# Tomo.net
KiCad netlist of a schematic drawn in EAGLE
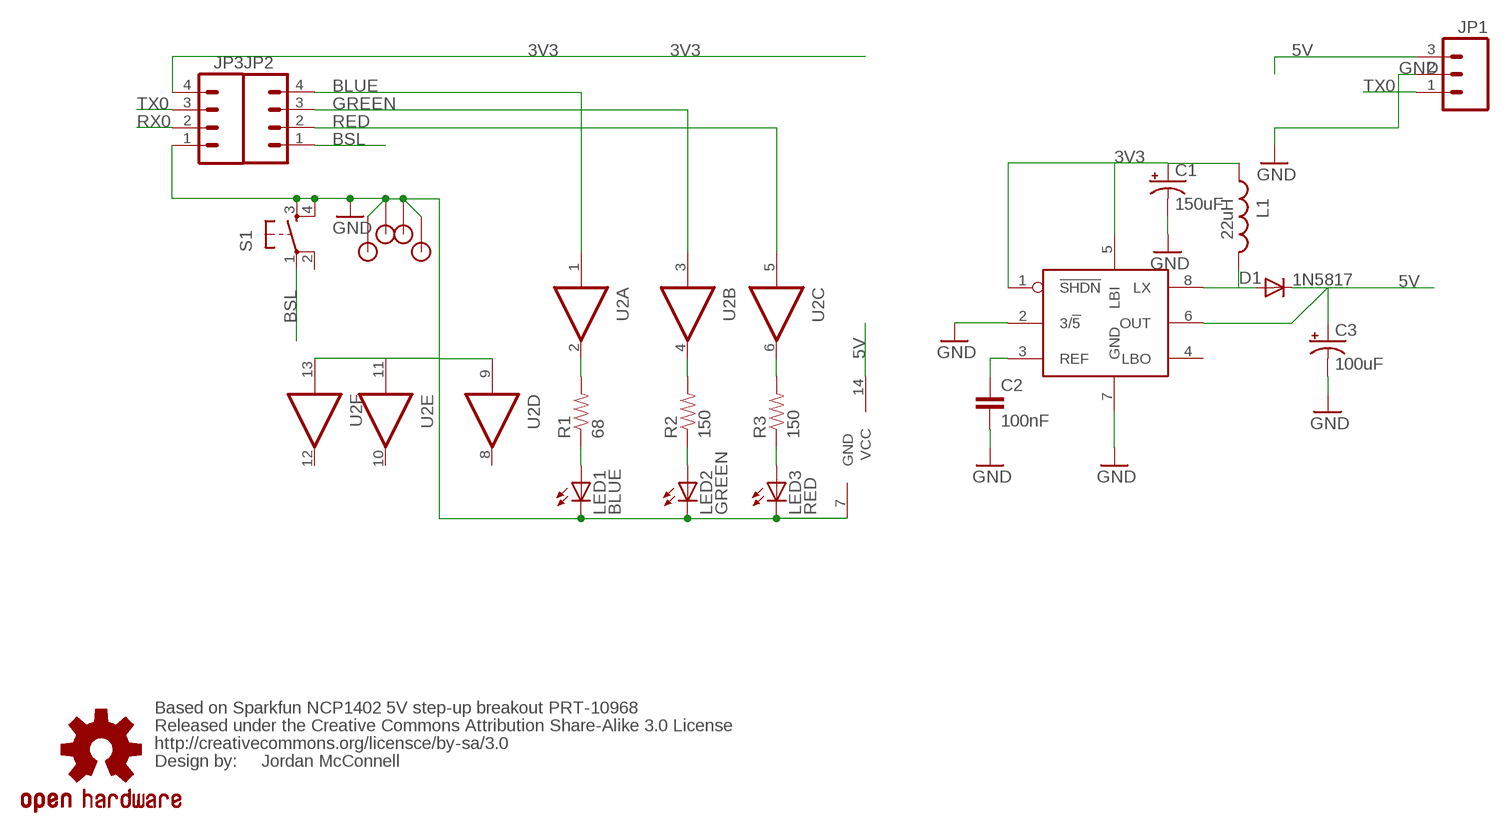
[diagram p0: schematic, sheet 1]

(export (version "E")
  (design (tool "Eeschema 10.0.6"))
  (components
    (comp (ref "C1")
      (value "150uF")
      (footprint "eagle-import:CPOL-RADIAL-100UF-25V")
      (libsource (lib "eagle-import") (part "CAP_POLPTH1"))
    )
    (comp (ref "C2")
      (value "100nF")
      (footprint "eagle-import:CAP-PTH-SMALL")
      (libsource (lib "eagle-import") (part "CAPPTH"))
    )
    (comp (ref "C3")
      (value "100uF")
      (footprint "eagle-import:CPOL-RADIAL-100UF-25V")
      (libsource (lib "eagle-import") (part "CAP_POLPTH1"))
    )
    (comp (ref "D1")
      (value "1N5817")
      (footprint "eagle-import:DIODE-1N4148")
      (libsource (lib "eagle-import") (part "DIODE1N4148"))
    )
    (comp (ref "JP1")
      (value "M03PTH")
      (footprint "eagle-import:1X03")
      (libsource (lib "eagle-import") (part "M03PTH"))
    )
    (comp (ref "JP2")
      (value "M04PTH")
      (footprint "eagle-import:1X04")
      (libsource (lib "eagle-import") (part "M04PTH"))
    )
    (comp (ref "JP3")
      (value "M04PTH")
      (footprint "eagle-import:1X04")
      (libsource (lib "eagle-import") (part "M04PTH"))
    )
    (comp (ref "L1")
      (value "22uH")
      (footprint "eagle-import:RADIAL_5MM")
      (libsource (lib "eagle-import") (part "INDUCTORRCH-895"))
    )
    (comp (ref "LED1")
      (value "BLUE")
      (footprint "eagle-import:LED5MM")
      (libsource (lib "eagle-import") (part "LED5MM"))
    )
    (comp (ref "LED2")
      (value "GREEN")
      (footprint "eagle-import:LED5MM")
      (libsource (lib "eagle-import") (part "LED5MM"))
    )
    (comp (ref "LED3")
      (value "RED")
      (footprint "eagle-import:LED5MM")
      (libsource (lib "eagle-import") (part "LED5MM"))
    )
    (comp (ref "R1")
      (value "68")
      (footprint "eagle-import:AXIAL-0.3")
      (libsource (lib "eagle-import") (part "RESISTORAXIAL-0.3"))
    )
    (comp (ref "R2")
      (value "150")
      (footprint "eagle-import:AXIAL-0.3")
      (libsource (lib "eagle-import") (part "RESISTORAXIAL-0.3"))
    )
    (comp (ref "R3")
      (value "150")
      (footprint "eagle-import:AXIAL-0.3")
      (libsource (lib "eagle-import") (part "RESISTORAXIAL-0.3"))
    )
    (comp (ref "S1")
      (value "TAC_SWITCHPTH")
      (footprint "eagle-import:TACTILE-PTH")
      (libsource (lib "eagle-import") (part "TAC_SWITCHPTH"))
    )
    (comp (ref "U$1")
      (value "OSHW-LOGOL")
      (footprint "eagle-import:OSHW-LOGO-L")
      (libsource (lib "eagle-import") (part "OSHW-LOGOL"))
    )
    (comp (ref "U$2")
      (value "MAX756")
      (footprint "eagle-import:DIL-8")
      (libsource (lib "eagle-import") (part "MAX756"))
    )
    (comp (ref "U$3")
      (value "STANDOFF")
      (footprint "eagle-import:STANDOFF")
      (libsource (lib "eagle-import") (part "STANDOFF"))
    )
    (comp (ref "U$4")
      (value "STANDOFF")
      (footprint "eagle-import:STANDOFF")
      (libsource (lib "eagle-import") (part "STANDOFF"))
    )
    (comp (ref "U$5")
      (value "STANDOFF")
      (footprint "eagle-import:STANDOFF")
      (libsource (lib "eagle-import") (part "STANDOFF"))
    )
    (comp (ref "U$6")
      (value "STANDOFF")
      (footprint "eagle-import:STANDOFF")
      (libsource (lib "eagle-import") (part "STANDOFF"))
    )
    (comp (ref "U2")
      (value "741034")
      (footprint "eagle-import:DIL-14")
      (fields (field (name "DIGIKEY") "296-33703-5-ND"))
      (libsource (lib "eagle-import") (part "741034"))
    )
  )
  (nets
    (net (code "1") (name "/3V3") (class "Default")
      (node (ref "C1") (pin "1") (pinfunction "+_1") (pintype "passive"))
      (node (ref "JP3") (pin "4") (pinfunction "4_4") (pintype "passive"))
      (node (ref "L1") (pin "1") (pinfunction "1_1") (pintype "passive"))
      (node (ref "U$2") (pin "1") (pinfunction "~{SHDN}_1") (pintype "bidirectional"))
      (node (ref "U$2") (pin "5") (pinfunction "LBI_5") (pintype "bidirectional"))
    )
    (net (code "2") (name "/5V") (class "Default")
      (node (ref "C3") (pin "1") (pinfunction "+_1") (pintype "passive"))
      (node (ref "D1") (pin "C") (pinfunction "C_C") (pintype "passive"))
      (node (ref "JP1") (pin "3") (pinfunction "3_3") (pintype "passive"))
      (node (ref "U$2") (pin "6") (pinfunction "OUT_6") (pintype "bidirectional"))
      (node (ref "U2") (pin "14") (pinfunction "VCC_14") (pintype "bidirectional"))
    )
    (net (code "3") (name "/BLUE") (class "Default")
      (node (ref "JP2") (pin "4") (pinfunction "4_4") (pintype "passive"))
      (node (ref "U2") (pin "1") (pinfunction "IN_1") (pintype "input"))
    )
    (net (code "4") (name "/BSL") (class "Default")
      (node (ref "JP2") (pin "1") (pinfunction "1_1") (pintype "passive"))
      (node (ref "S1") (pin "1") (pinfunction "1_1") (pintype "passive"))
    )
    (net (code "5") (name "/GREEN") (class "Default")
      (node (ref "JP2") (pin "3") (pinfunction "3_3") (pintype "passive"))
      (node (ref "U2") (pin "3") (pinfunction "IN_3") (pintype "input"))
    )
    (net (code "6") (name "/RED") (class "Default")
      (node (ref "JP2") (pin "2") (pinfunction "2_2") (pintype "passive"))
      (node (ref "U2") (pin "5") (pinfunction "IN_5") (pintype "input"))
    )
    (net (code "7") (name "/RX0") (class "Default")
      (node (ref "JP3") (pin "2") (pinfunction "2_2") (pintype "passive"))
    )
    (net (code "8") (name "/TX0") (class "Default")
      (node (ref "JP1") (pin "1") (pinfunction "1_1") (pintype "passive"))
      (node (ref "JP3") (pin "3") (pinfunction "3_3") (pintype "passive"))
    )
    (net (code "9") (name "GND") (class "Default")
      (node (ref "C1") (pin "2") (pinfunction "-_2") (pintype "passive"))
      (node (ref "C2") (pin "2") (pinfunction "2_2") (pintype "passive"))
      (node (ref "C3") (pin "2") (pinfunction "-_2") (pintype "passive"))
      (node (ref "JP1") (pin "2") (pinfunction "2_2") (pintype "passive"))
      (node (ref "JP3") (pin "1") (pinfunction "1_1") (pintype "passive"))
      (node (ref "LED1") (pin "K") (pinfunction "C_K") (pintype "passive"))
      (node (ref "LED2") (pin "K") (pinfunction "C_K") (pintype "passive"))
      (node (ref "LED3") (pin "K") (pinfunction "C_K") (pintype "passive"))
      (node (ref "S1") (pin "3") (pinfunction "3_3") (pintype "passive"))
      (node (ref "S1") (pin "4") (pinfunction "4_4") (pintype "passive"))
      (node (ref "U$2") (pin "2") (pinfunction "3/~{5}_2") (pintype "bidirectional"))
      (node (ref "U$2") (pin "7") (pinfunction "GND_7") (pintype "bidirectional"))
      (node (ref "U$3") (pin "P$1") (pinfunction "P$1_P$1") (pintype "bidirectional"))
      (node (ref "U$4") (pin "P$1") (pinfunction "P$1_P$1") (pintype "bidirectional"))
      (node (ref "U$5") (pin "P$1") (pinfunction "P$1_P$1") (pintype "bidirectional"))
      (node (ref "U$6") (pin "P$1") (pinfunction "P$1_P$1") (pintype "bidirectional"))
      (node (ref "U2") (pin "11") (pinfunction "IN_11") (pintype "input"))
      (node (ref "U2") (pin "13") (pinfunction "IN_13") (pintype "input"))
      (node (ref "U2") (pin "7") (pinfunction "GND_7") (pintype "bidirectional"))
      (node (ref "U2") (pin "9") (pinfunction "IN_9") (pintype "input"))
    )
    (net (code "10") (name "Net-(R1-1)") (class "Default")
      (node (ref "LED1") (pin "A") (pinfunction "A_A") (pintype "passive"))
      (node (ref "R1") (pin "P$1") (pinfunction "1_P$1") (pintype "passive"))
    )
    (net (code "11") (name "Net-(R1-2)") (class "Default")
      (node (ref "R1") (pin "P$2") (pinfunction "2_P$2") (pintype "passive"))
      (node (ref "U2") (pin "2") (pinfunction "OUT_2") (pintype "bidirectional"))
    )
    (net (code "12") (name "Net-(R2-1)") (class "Default")
      (node (ref "LED2") (pin "A") (pinfunction "A_A") (pintype "passive"))
      (node (ref "R2") (pin "P$1") (pinfunction "1_P$1") (pintype "passive"))
    )
    (net (code "13") (name "Net-(R2-2)") (class "Default")
      (node (ref "R2") (pin "P$2") (pinfunction "2_P$2") (pintype "passive"))
      (node (ref "U2") (pin "4") (pinfunction "OUT_4") (pintype "bidirectional"))
    )
    (net (code "14") (name "Net-(R3-1)") (class "Default")
      (node (ref "LED3") (pin "A") (pinfunction "A_A") (pintype "passive"))
      (node (ref "R3") (pin "P$1") (pinfunction "1_P$1") (pintype "passive"))
    )
    (net (code "15") (name "Net-(R3-2)") (class "Default")
      (node (ref "R3") (pin "P$2") (pinfunction "2_P$2") (pintype "passive"))
      (node (ref "U2") (pin "6") (pinfunction "OUT_6") (pintype "bidirectional"))
    )
    (net (code "16") (name "Net-(U$2-LX)") (class "Default")
      (node (ref "D1") (pin "A") (pinfunction "A_A") (pintype "passive"))
      (node (ref "L1") (pin "2") (pinfunction "2_2") (pintype "passive"))
      (node (ref "U$2") (pin "8") (pinfunction "LX_8") (pintype "bidirectional"))
    )
    (net (code "17") (name "Net-(U$2-REF)") (class "Default")
      (node (ref "C2") (pin "1") (pinfunction "1_1") (pintype "passive"))
      (node (ref "U$2") (pin "3") (pinfunction "REF_3") (pintype "bidirectional"))
    )
    (net (code "18") (name "unconnected-(S1-Pad2)") (class "Default")
      (node (ref "S1") (pin "2") (pinfunction "2_2") (pintype "passive"))
    )
    (net (code "19") (name "unconnected-(U$2-LBO-Pad4)") (class "Default")
      (node (ref "U$2") (pin "4") (pinfunction "LBO_4") (pintype "bidirectional"))
    )
    (net (code "20") (name "unconnected-(U2D-OUT-Pad8)") (class "Default")
      (node (ref "U2") (pin "8") (pinfunction "OUT_8") (pintype "bidirectional"))
    )
    (net (code "21") (name "unconnected-(U2E-OUT-Pad10)") (class "Default")
      (node (ref "U2") (pin "10") (pinfunction "OUT_10") (pintype "bidirectional"))
    )
    (net (code "22") (name "unconnected-(U2F-OUT-Pad12)") (class "Default")
      (node (ref "U2") (pin "12") (pinfunction "OUT_12") (pintype "bidirectional"))
    )
  )
)
